# MQ-135.net
KiCad netlist of a schematic drawn in Altium Designer
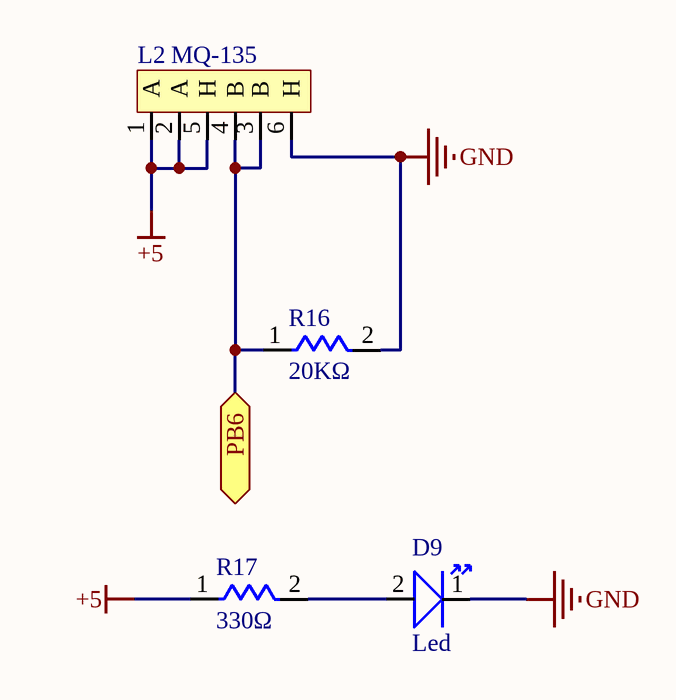
[diagram p0: MQ-135.SchDoc]

(export (version "E")
  (design (tool "Eeschema 10.0.6"))
  (components
    (comp (ref "D9")
      (value "Led")
      (footprint "LED - 0603")
      (description "HL-PST-1608U51GC - LED SMD 0603 GREEN 500mcd 120° WATER CLEAR")
      (libsource (lib "Faydali_Yuk_Schlib1") (part "Led"))
    )
    (comp (ref "L2")
      (value "MQ-135")
      (footprint "MQ-135")
      (libsource (lib "Faydali_Yuk_Schlib1") (part "MQ-135"))
    )
    (comp (ref "R16")
      (value "20KΩ")
      (footprint "RES - 0603")
      (description "SMD Res")
      (libsource (lib "Faydali_Yuk_Schlib1") (part "Res"))
    )
    (comp (ref "R17")
      (value "330Ω")
      (footprint "RES - 0603")
      (description "SMD Res")
      (libsource (lib "Faydali_Yuk_Schlib1") (part "Res"))
    )
  )
  (nets
    (net (code "1") (name "+5") (class "Default")
      (node (ref "L2") (pin "1") (pinfunction "A_1") (pintype "passive"))
      (node (ref "L2") (pin "2") (pinfunction "A_2") (pintype "passive"))
      (node (ref "L2") (pin "5") (pinfunction "H_5") (pintype "passive"))
      (node (ref "R17") (pin "1") (pinfunction "1_1") (pintype "passive"))
    )
    (net (code "2") (name "/PB6") (class "Default")
      (node (ref "L2") (pin "3") (pinfunction "B_3") (pintype "passive"))
      (node (ref "L2") (pin "4") (pinfunction "B_4") (pintype "passive"))
      (node (ref "R16") (pin "1") (pinfunction "1_1") (pintype "passive"))
    )
    (net (code "3") (name "GND") (class "Default")
      (node (ref "D9") (pin "1") (pinfunction "1_1") (pintype "passive"))
      (node (ref "L2") (pin "6") (pinfunction "H_6") (pintype "passive"))
      (node (ref "R16") (pin "2") (pinfunction "2_2") (pintype "passive"))
    )
    (net (code "4") (name "Net-(D9-Pad2)") (class "Default")
      (node (ref "D9") (pin "2") (pinfunction "2_2") (pintype "passive"))
      (node (ref "R17") (pin "2") (pinfunction "2_2") (pintype "passive"))
    )
  )
)
